# rapidshark-battery-conn-mk-1_1.net
KiCad netlist of a schematic drawn in EAGLE
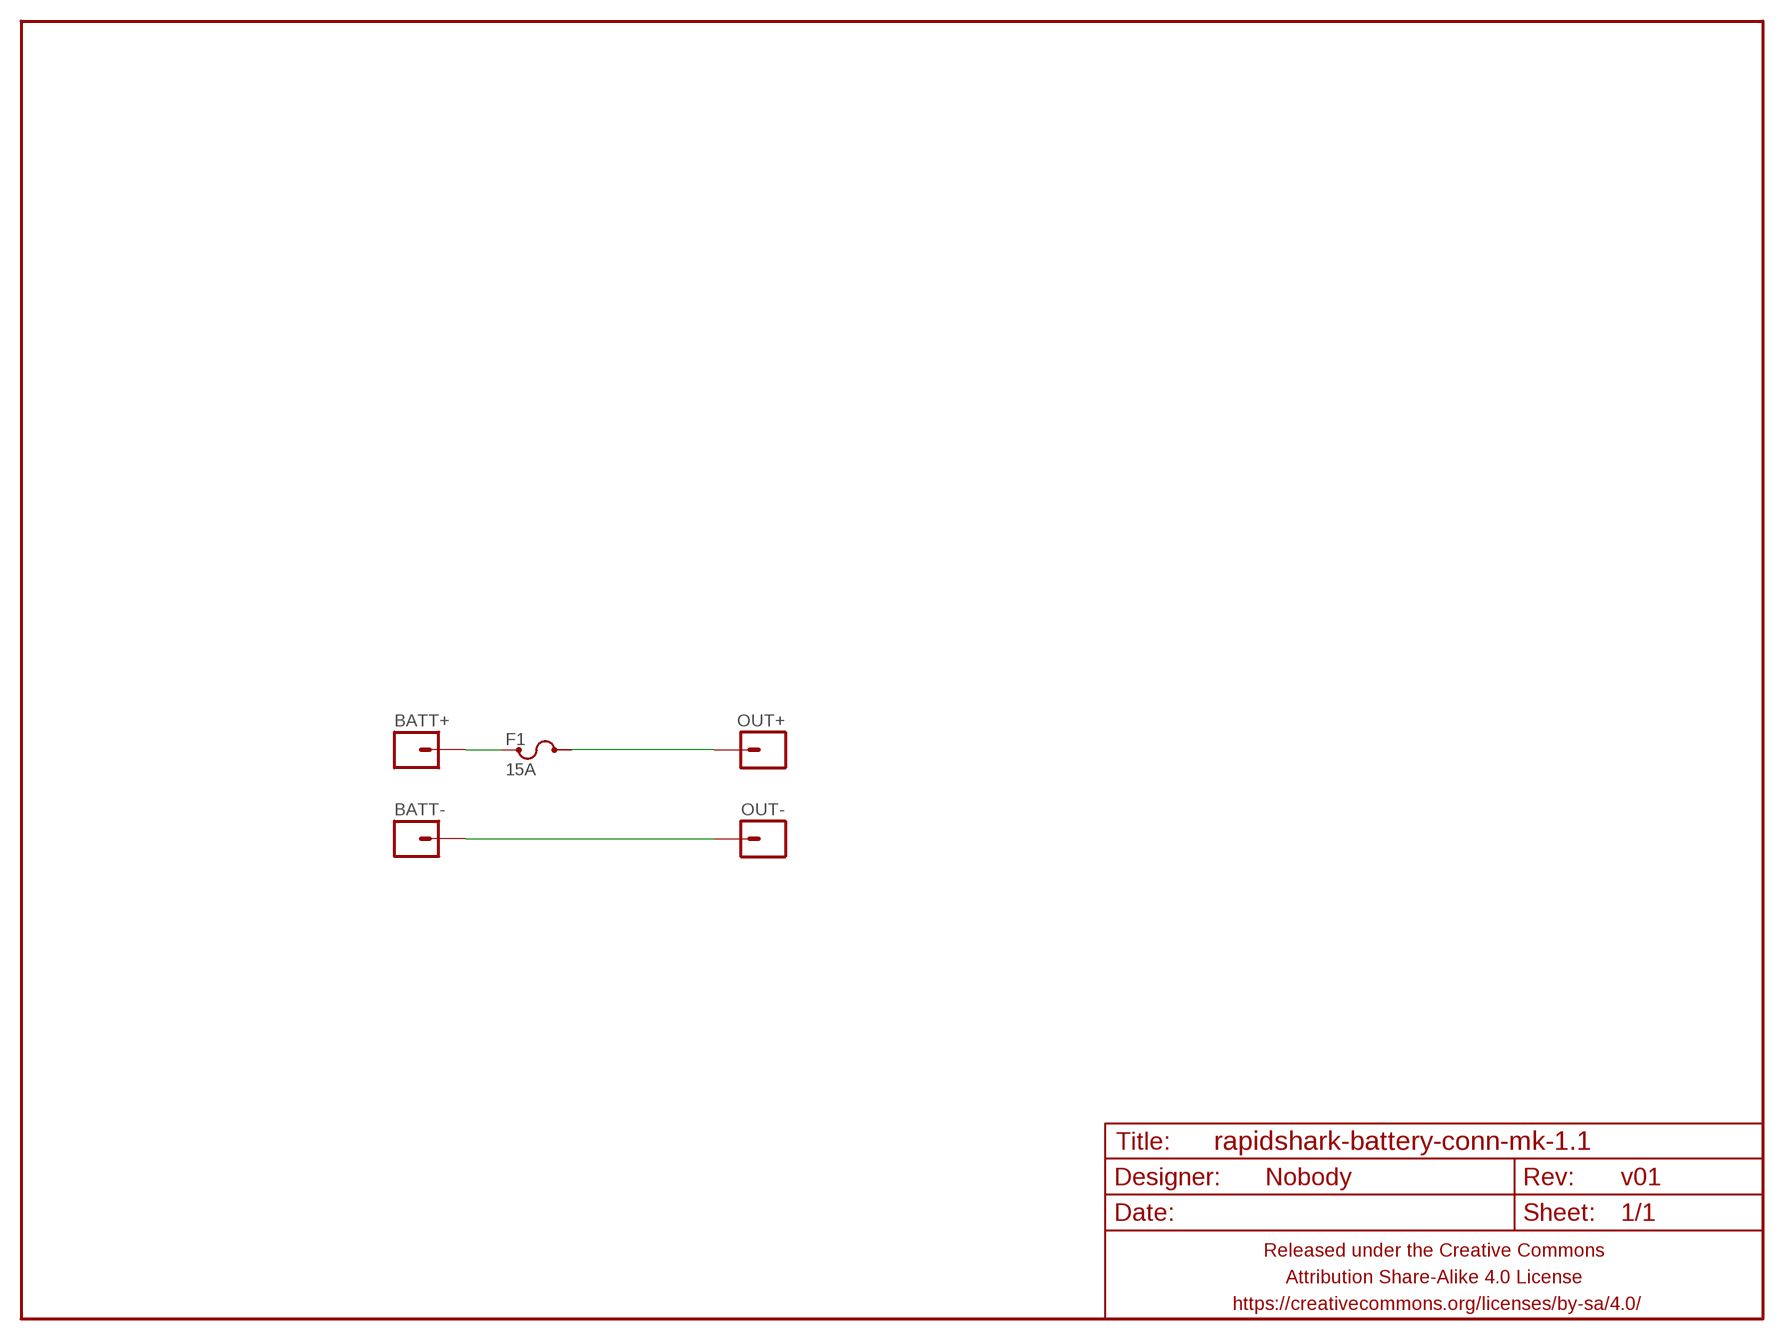
[diagram p0: schematic, sheet 1]

(export (version "E")
  (design (tool "Eeschema 10.0.6"))
  (components
    (comp (ref "BATT+")
      (value "M01PTH-2.3MM")
      (footprint "eagle-import:1X01-2.3MM")
      (libsource (lib "eagle-import") (part "M01PTH-2.3MM"))
    )
    (comp (ref "BATT-")
      (value "M01PTH-2.3MM")
      (footprint "eagle-import:1X01-2.3MM")
      (libsource (lib "eagle-import") (part "M01PTH-2.3MM"))
    )
    (comp (ref "F1")
      (value "15A")
      (footprint "eagle-import:KEYSTONE-MINI-AUTO-FUSE-HOLDER")
      (libsource (lib "eagle-import") (part "FUSEMINI-AUTO"))
    )
    (comp (ref "FRAME1")
      (value "FRAME-LETTERNO_PACKAGE")
      (footprint "eagle-import:DUMMY")
      (fields (field (name "DESIGNER") "Nobody"))
      (libsource (lib "eagle-import") (part "FRAME-LETTERNO_PACKAGE"))
    )
    (comp (ref "OUT+")
      (value "M0112AWG")
      (footprint "eagle-import:1X01-12AWG")
      (libsource (lib "eagle-import") (part "M0112AWG"))
    )
    (comp (ref "OUT-")
      (value "M0112AWG")
      (footprint "eagle-import:1X01-12AWG")
      (libsource (lib "eagle-import") (part "M0112AWG"))
    )
  )
  (nets
    (net (code "1") (name "Net-(BATT+-Pad1)") (class "Default")
      (node (ref "BATT+") (pin "1") (pinfunction "1_1") (pintype "passive"))
      (node (ref "F1") (pin "P1@1") (pinfunction "1_P1@1") (pintype "passive"))
      (node (ref "F1") (pin "P1@2") (pinfunction "1_P1@2") (pintype "passive"))
    )
    (net (code "2") (name "Net-(BATT--Pad1)") (class "Default")
      (node (ref "BATT-") (pin "1") (pinfunction "1_1") (pintype "passive"))
      (node (ref "OUT-") (pin "1") (pinfunction "1_1") (pintype "passive"))
    )
    (net (code "3") (name "Net-(F1-2-PadP2@1)") (class "Default")
      (node (ref "F1") (pin "P2@1") (pinfunction "2_P2@1") (pintype "passive"))
      (node (ref "F1") (pin "P2@2") (pinfunction "2_P2@2") (pintype "passive"))
      (node (ref "OUT+") (pin "1") (pinfunction "1_1") (pintype "passive"))
    )
  )
)
